# rb03.net
KiCad netlist of a schematic drawn in EAGLE
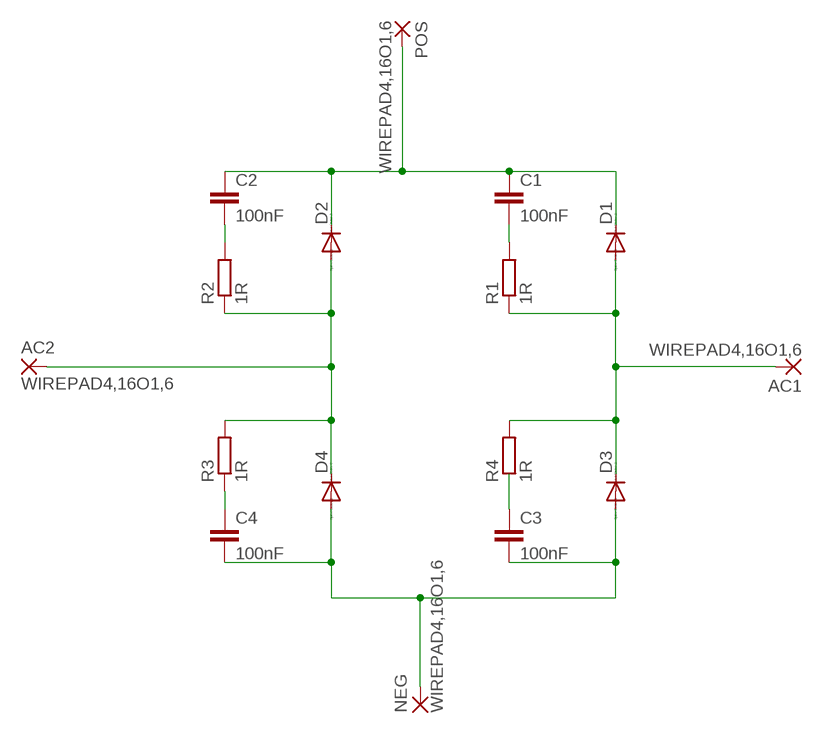
[diagram p0: schematic, sheet 1]

(export (version "E")
  (design (tool "Eeschema 10.0.6"))
  (components
    (comp (ref "AC1")
      (value "WIREPAD4,16O1,6")
      (footprint "eagle-import:4,16O1,6")
      (libsource (lib "eagle-import") (part "WIREPAD4,16O1,6"))
    )
    (comp (ref "AC2")
      (value "WIREPAD4,16O1,6")
      (footprint "eagle-import:4,16O1,6")
      (libsource (lib "eagle-import") (part "WIREPAD4,16O1,6"))
    )
    (comp (ref "C1")
      (value "100nF")
      (footprint "eagle-import:C150-084X183")
      (libsource (lib "eagle-import") (part "C-EU150-084X183"))
    )
    (comp (ref "C2")
      (value "100nF")
      (footprint "eagle-import:C150-084X183")
      (libsource (lib "eagle-import") (part "C-EU150-084X183"))
    )
    (comp (ref "C3")
      (value "100nF")
      (footprint "eagle-import:C150-084X183")
      (libsource (lib "eagle-import") (part "C-EU150-084X183"))
    )
    (comp (ref "C4")
      (value "100nF")
      (footprint "eagle-import:C150-084X183")
      (libsource (lib "eagle-import") (part "C-EU150-084X183"))
    )
    (comp (ref "D1")
      (value "DIODE-TO220V")
      (footprint "eagle-import:TO220ACS")
      (libsource (lib "eagle-import") (part "DIODE-TO220V"))
    )
    (comp (ref "D2")
      (value "DIODE-TO220V")
      (footprint "eagle-import:TO220ACS")
      (libsource (lib "eagle-import") (part "DIODE-TO220V"))
    )
    (comp (ref "D3")
      (value "DIODE-TO220V")
      (footprint "eagle-import:TO220ACS")
      (libsource (lib "eagle-import") (part "DIODE-TO220V"))
    )
    (comp (ref "D4")
      (value "DIODE-TO220V")
      (footprint "eagle-import:TO220ACS")
      (libsource (lib "eagle-import") (part "DIODE-TO220V"))
    )
    (comp (ref "NEG")
      (value "WIREPAD4,16O1,6")
      (footprint "eagle-import:4,16O1,6")
      (libsource (lib "eagle-import") (part "WIREPAD4,16O1,6"))
    )
    (comp (ref "POS")
      (value "WIREPAD4,16O1,6")
      (footprint "eagle-import:4,16O1,6")
      (libsource (lib "eagle-import") (part "WIREPAD4,16O1,6"))
    )
    (comp (ref "R1")
      (value "1R")
      (footprint "eagle-import:0207_10")
      (libsource (lib "eagle-import") (part "R-EU_0207/10"))
    )
    (comp (ref "R2")
      (value "1R")
      (footprint "eagle-import:0207_10")
      (libsource (lib "eagle-import") (part "R-EU_0207/10"))
    )
    (comp (ref "R3")
      (value "1R")
      (footprint "eagle-import:0207_10")
      (libsource (lib "eagle-import") (part "R-EU_0207/10"))
    )
    (comp (ref "R4")
      (value "1R")
      (footprint "eagle-import:0207_10")
      (libsource (lib "eagle-import") (part "R-EU_0207/10"))
    )
  )
  (nets
    (net (code "1") (name "Net-(AC1-P)") (class "Default")
      (node (ref "AC1") (pin "1") (pinfunction "P_1") (pintype "passive"))
      (node (ref "D1") (pin "A") (pinfunction "A_A") (pintype "passive"))
      (node (ref "D3") (pin "C") (pinfunction "C_C") (pintype "passive"))
      (node (ref "R1") (pin "1") (pinfunction "1_1") (pintype "passive"))
      (node (ref "R4") (pin "2") (pinfunction "2_2") (pintype "passive"))
    )
    (net (code "2") (name "Net-(AC2-P)") (class "Default")
      (node (ref "AC2") (pin "1") (pinfunction "P_1") (pintype "passive"))
      (node (ref "D2") (pin "A") (pinfunction "A_A") (pintype "passive"))
      (node (ref "D4") (pin "C") (pinfunction "C_C") (pintype "passive"))
      (node (ref "R2") (pin "1") (pinfunction "1_1") (pintype "passive"))
      (node (ref "R3") (pin "2") (pinfunction "2_2") (pintype "passive"))
    )
    (net (code "3") (name "Net-(C1-Pad2)") (class "Default")
      (node (ref "C1") (pin "2") (pinfunction "2_2") (pintype "passive"))
      (node (ref "R1") (pin "2") (pinfunction "2_2") (pintype "passive"))
    )
    (net (code "4") (name "Net-(C2-Pad2)") (class "Default")
      (node (ref "C2") (pin "2") (pinfunction "2_2") (pintype "passive"))
      (node (ref "R2") (pin "2") (pinfunction "2_2") (pintype "passive"))
    )
    (net (code "5") (name "Net-(C4-Pad1)") (class "Default")
      (node (ref "C4") (pin "1") (pinfunction "1_1") (pintype "passive"))
      (node (ref "R3") (pin "1") (pinfunction "1_1") (pintype "passive"))
    )
    (net (code "6") (name "Net-(NEG-P)") (class "Default")
      (node (ref "C3") (pin "2") (pinfunction "2_2") (pintype "passive"))
      (node (ref "C4") (pin "2") (pinfunction "2_2") (pintype "passive"))
      (node (ref "D3") (pin "A") (pinfunction "A_A") (pintype "passive"))
      (node (ref "D4") (pin "A") (pinfunction "A_A") (pintype "passive"))
      (node (ref "NEG") (pin "1") (pinfunction "P_1") (pintype "passive"))
    )
    (net (code "7") (name "Net-(POS-P)") (class "Default")
      (node (ref "C1") (pin "1") (pinfunction "1_1") (pintype "passive"))
      (node (ref "C2") (pin "1") (pinfunction "1_1") (pintype "passive"))
      (node (ref "D1") (pin "C") (pinfunction "C_C") (pintype "passive"))
      (node (ref "D2") (pin "C") (pinfunction "C_C") (pintype "passive"))
      (node (ref "POS") (pin "1") (pinfunction "P_1") (pintype "passive"))
    )
    (net (code "8") (name "unconnected-(C3-Pad1)") (class "Default")
      (node (ref "C3") (pin "1") (pinfunction "1_1") (pintype "passive"))
    )
    (net (code "9") (name "unconnected-(R4-Pad1)") (class "Default")
      (node (ref "R4") (pin "1") (pinfunction "1_1") (pintype "passive"))
    )
  )
)
